# Digital_Inputs.net
KiCad netlist of a schematic drawn in Altium Designer
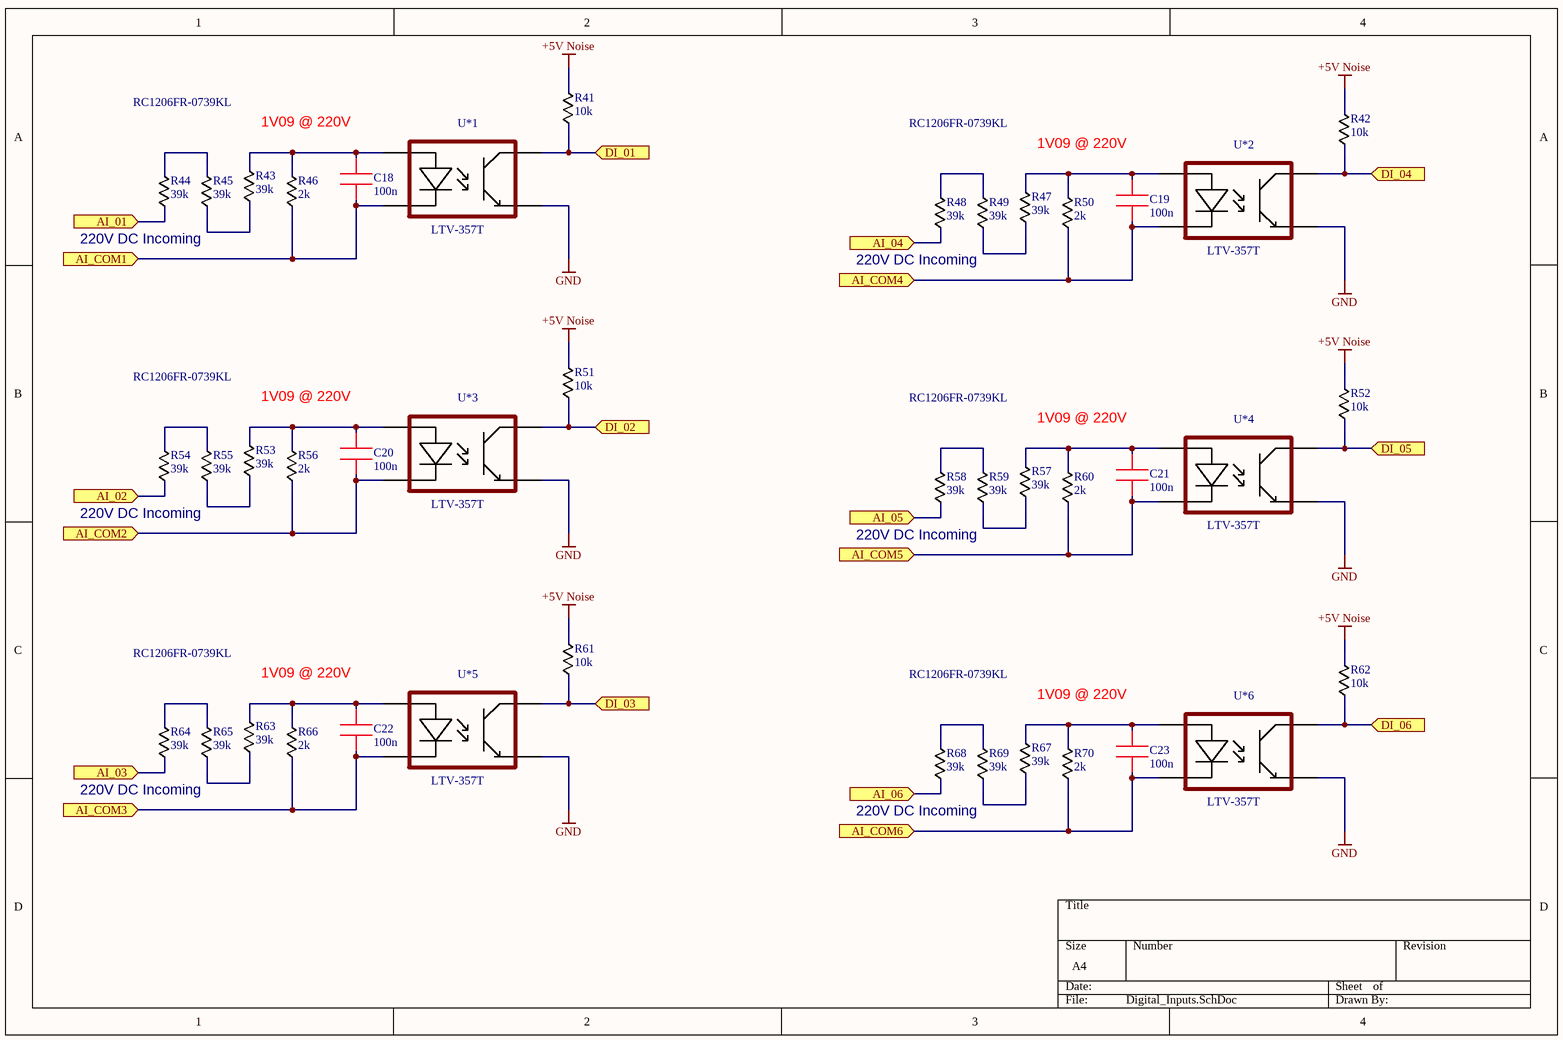
[diagram p0: Digital_Inputs.SchDoc]

(export (version "E")
  (design (tool "Eeschema 10.0.6"))
  (components
    (comp (ref "C18")
      (value "100n")
      (footprint "0603")
      (description "CC0603KRX7R9BB104")
      (libsource (lib "kontr") (part "0603 CAP"))
    )
    (comp (ref "C19")
      (value "100n")
      (footprint "0603")
      (description "CC0603KRX7R9BB104")
      (libsource (lib "kontr") (part "0603 CAP"))
    )
    (comp (ref "C20")
      (value "100n")
      (footprint "0603")
      (description "CC0603KRX7R9BB104")
      (libsource (lib "kontr") (part "0603 CAP"))
    )
    (comp (ref "C21")
      (value "100n")
      (footprint "0603")
      (description "CC0603KRX7R9BB104")
      (libsource (lib "kontr") (part "0603 CAP"))
    )
    (comp (ref "C22")
      (value "100n")
      (footprint "0603")
      (description "CC0603KRX7R9BB104")
      (libsource (lib "kontr") (part "0603 CAP"))
    )
    (comp (ref "C23")
      (value "100n")
      (footprint "0603")
      (description "CC0603KRX7R9BB104")
      (libsource (lib "kontr") (part "0603 CAP"))
    )
    (comp (ref "R41")
      (value "10k")
      (footprint "0603")
      (description "RT0603FRE0710KL")
      (libsource (lib "kontr") (part "0603 RES"))
    )
    (comp (ref "R42")
      (value "10k")
      (footprint "0603")
      (description "RT0603FRE0710KL")
      (libsource (lib "kontr") (part "0603 RES"))
    )
    (comp (ref "R43")
      (value "39k")
      (footprint "1206")
      (description "RC1206FR-0739KL")
      (libsource (lib "kontr") (part "1206 R"))
    )
    (comp (ref "R44")
      (value "39k")
      (footprint "1206")
      (description "RC1206FR-0739KL")
      (libsource (lib "kontr") (part "1206 R"))
    )
    (comp (ref "R45")
      (value "39k")
      (footprint "1206")
      (description "RC1206FR-0739KL")
      (libsource (lib "kontr") (part "1206 R"))
    )
    (comp (ref "R46")
      (value "2k")
      (footprint "1206")
      (description "RC1206FR-072KL")
      (libsource (lib "kontr") (part "1206 R"))
    )
    (comp (ref "R47")
      (value "39k")
      (footprint "1206")
      (description "RC1206FR-0739KL")
      (libsource (lib "kontr") (part "1206 R"))
    )
    (comp (ref "R48")
      (value "39k")
      (footprint "1206")
      (description "RC1206FR-0739KL")
      (libsource (lib "kontr") (part "1206 R"))
    )
    (comp (ref "R49")
      (value "39k")
      (footprint "1206")
      (description "RC1206FR-0739KL")
      (libsource (lib "kontr") (part "1206 R"))
    )
    (comp (ref "R50")
      (value "2k")
      (footprint "1206")
      (description "RC1206FR-072KL")
      (libsource (lib "kontr") (part "1206 R"))
    )
    (comp (ref "R51")
      (value "10k")
      (footprint "0603")
      (description "RT0603FRE0710KL")
      (libsource (lib "kontr") (part "0603 RES"))
    )
    (comp (ref "R52")
      (value "10k")
      (footprint "0603")
      (description "RT0603FRE0710KL")
      (libsource (lib "kontr") (part "0603 RES"))
    )
    (comp (ref "R53")
      (value "39k")
      (footprint "1206")
      (description "RC1206FR-0739KL")
      (libsource (lib "kontr") (part "1206 R"))
    )
    (comp (ref "R54")
      (value "39k")
      (footprint "1206")
      (description "RC1206FR-0739KL")
      (libsource (lib "kontr") (part "1206 R"))
    )
    (comp (ref "R55")
      (value "39k")
      (footprint "1206")
      (description "RC1206FR-0739KL")
      (libsource (lib "kontr") (part "1206 R"))
    )
    (comp (ref "R56")
      (value "2k")
      (footprint "1206")
      (description "RC1206FR-072KL")
      (libsource (lib "kontr") (part "1206 R"))
    )
    (comp (ref "R57")
      (value "39k")
      (footprint "1206")
      (description "RC1206FR-0739KL")
      (libsource (lib "kontr") (part "1206 R"))
    )
    (comp (ref "R58")
      (value "39k")
      (footprint "1206")
      (description "RC1206FR-0739KL")
      (libsource (lib "kontr") (part "1206 R"))
    )
    (comp (ref "R59")
      (value "39k")
      (footprint "1206")
      (description "RC1206FR-0739KL")
      (libsource (lib "kontr") (part "1206 R"))
    )
    (comp (ref "R60")
      (value "2k")
      (footprint "1206")
      (description "RC1206FR-072KL")
      (libsource (lib "kontr") (part "1206 R"))
    )
    (comp (ref "R61")
      (value "10k")
      (footprint "0603")
      (description "RT0603FRE0710KL")
      (libsource (lib "kontr") (part "0603 RES"))
    )
    (comp (ref "R62")
      (value "10k")
      (footprint "0603")
      (description "RT0603FRE0710KL")
      (libsource (lib "kontr") (part "0603 RES"))
    )
    (comp (ref "R63")
      (value "39k")
      (footprint "1206")
      (description "RC1206FR-0739KL")
      (libsource (lib "kontr") (part "1206 R"))
    )
    (comp (ref "R64")
      (value "39k")
      (footprint "1206")
      (description "RC1206FR-0739KL")
      (libsource (lib "kontr") (part "1206 R"))
    )
    (comp (ref "R65")
      (value "39k")
      (footprint "1206")
      (description "RC1206FR-0739KL")
      (libsource (lib "kontr") (part "1206 R"))
    )
    (comp (ref "R66")
      (value "2k")
      (footprint "1206")
      (description "RC1206FR-072KL")
      (libsource (lib "kontr") (part "1206 R"))
    )
    (comp (ref "R67")
      (value "39k")
      (footprint "1206")
      (description "RC1206FR-0739KL")
      (libsource (lib "kontr") (part "1206 R"))
    )
    (comp (ref "R68")
      (value "39k")
      (footprint "1206")
      (description "RC1206FR-0739KL")
      (libsource (lib "kontr") (part "1206 R"))
    )
    (comp (ref "R69")
      (value "39k")
      (footprint "1206")
      (description "RC1206FR-0739KL")
      (libsource (lib "kontr") (part "1206 R"))
    )
    (comp (ref "R70")
      (value "2k")
      (footprint "1206")
      (description "RC1206FR-072KL")
      (libsource (lib "kontr") (part "1206 R"))
    )
    (comp (ref "U*1")
      (value "LTV-357T")
      (footprint "levin:SOP-4")
      (libsource (lib "levin") (part "LTV-357T"))
    )
    (comp (ref "U*2")
      (value "LTV-357T")
      (footprint "levin:SOP-4")
      (libsource (lib "levin") (part "LTV-357T"))
    )
    (comp (ref "U*3")
      (value "LTV-357T")
      (footprint "levin:SOP-4")
      (libsource (lib "levin") (part "LTV-357T"))
    )
    (comp (ref "U*4")
      (value "LTV-357T")
      (footprint "levin:SOP-4")
      (libsource (lib "levin") (part "LTV-357T"))
    )
    (comp (ref "U*5")
      (value "LTV-357T")
      (footprint "levin:SOP-4")
      (libsource (lib "levin") (part "LTV-357T"))
    )
    (comp (ref "U*6")
      (value "LTV-357T")
      (footprint "levin:SOP-4")
      (libsource (lib "levin") (part "LTV-357T"))
    )
  )
  (nets
    (net (code "1") (name "+5V Noise") (class "Default")
      (node (ref "R41") (pin "2") (pintype "passive"))
      (node (ref "R42") (pin "2") (pintype "passive"))
      (node (ref "R51") (pin "2") (pintype "passive"))
      (node (ref "R52") (pin "2") (pintype "passive"))
      (node (ref "R61") (pin "2") (pintype "passive"))
      (node (ref "R62") (pin "2") (pintype "passive"))
    )
    (net (code "2") (name "/AI_01") (class "Default") (node (ref "R44") (pin "1") (pintype "passive")))
    (net (code "3") (name "/AI_02") (class "Default") (node (ref "R54") (pin "1") (pintype "passive")))
    (net (code "4") (name "/AI_03") (class "Default") (node (ref "R64") (pin "1") (pintype "passive")))
    (net (code "5") (name "/AI_04") (class "Default") (node (ref "R48") (pin "1") (pintype "passive")))
    (net (code "6") (name "/AI_05") (class "Default") (node (ref "R58") (pin "1") (pintype "passive")))
    (net (code "7") (name "/AI_06") (class "Default") (node (ref "R68") (pin "1") (pintype "passive")))
    (net (code "8") (name "/AI_COM1") (class "Default")
      (node (ref "C18") (pin "1") (pinfunction "1_1") (pintype "passive"))
      (node (ref "R46") (pin "1") (pintype "passive"))
      (node (ref "U*1") (pin "Cathode") (pinfunction "C_Cathode") (pintype "passive"))
    )
    (net (code "9") (name "/AI_COM2") (class "Default")
      (node (ref "C20") (pin "1") (pinfunction "1_1") (pintype "passive"))
      (node (ref "R56") (pin "1") (pintype "passive"))
      (node (ref "U*3") (pin "Cathode") (pinfunction "C_Cathode") (pintype "passive"))
    )
    (net (code "10") (name "/AI_COM3") (class "Default")
      (node (ref "C22") (pin "1") (pinfunction "1_1") (pintype "passive"))
      (node (ref "R66") (pin "1") (pintype "passive"))
      (node (ref "U*5") (pin "Cathode") (pinfunction "C_Cathode") (pintype "passive"))
    )
    (net (code "11") (name "/AI_COM4") (class "Default")
      (node (ref "C19") (pin "1") (pinfunction "1_1") (pintype "passive"))
      (node (ref "R50") (pin "1") (pintype "passive"))
      (node (ref "U*2") (pin "Cathode") (pinfunction "C_Cathode") (pintype "passive"))
    )
    (net (code "12") (name "/AI_COM5") (class "Default")
      (node (ref "C21") (pin "1") (pinfunction "1_1") (pintype "passive"))
      (node (ref "R60") (pin "1") (pintype "passive"))
      (node (ref "U*4") (pin "Cathode") (pinfunction "C_Cathode") (pintype "passive"))
    )
    (net (code "13") (name "/AI_COM6") (class "Default")
      (node (ref "C23") (pin "1") (pinfunction "1_1") (pintype "passive"))
      (node (ref "R70") (pin "1") (pintype "passive"))
      (node (ref "U*6") (pin "Cathode") (pinfunction "C_Cathode") (pintype "passive"))
    )
    (net (code "14") (name "/DI_01") (class "Default")
      (node (ref "R41") (pin "1") (pintype "passive"))
      (node (ref "U*1") (pin "Collector") (pinfunction "C_Collector") (pintype "passive"))
    )
    (net (code "15") (name "/DI_02") (class "Default")
      (node (ref "R51") (pin "1") (pintype "passive"))
      (node (ref "U*3") (pin "Collector") (pinfunction "C_Collector") (pintype "passive"))
    )
    (net (code "16") (name "/DI_03") (class "Default")
      (node (ref "R61") (pin "1") (pintype "passive"))
      (node (ref "U*5") (pin "Collector") (pinfunction "C_Collector") (pintype "passive"))
    )
    (net (code "17") (name "/DI_04") (class "Default")
      (node (ref "R42") (pin "1") (pintype "passive"))
      (node (ref "U*2") (pin "Collector") (pinfunction "C_Collector") (pintype "passive"))
    )
    (net (code "18") (name "/DI_05") (class "Default")
      (node (ref "R52") (pin "1") (pintype "passive"))
      (node (ref "U*4") (pin "Collector") (pinfunction "C_Collector") (pintype "passive"))
    )
    (net (code "19") (name "/DI_06") (class "Default")
      (node (ref "R62") (pin "1") (pintype "passive"))
      (node (ref "U*6") (pin "Collector") (pinfunction "C_Collector") (pintype "passive"))
    )
    (net (code "20") (name "GND") (class "Default")
      (node (ref "U*1") (pin "Emmiter") (pinfunction "E_Emmiter") (pintype "passive"))
      (node (ref "U*2") (pin "Emmiter") (pinfunction "E_Emmiter") (pintype "passive"))
      (node (ref "U*3") (pin "Emmiter") (pinfunction "E_Emmiter") (pintype "passive"))
      (node (ref "U*4") (pin "Emmiter") (pinfunction "E_Emmiter") (pintype "passive"))
      (node (ref "U*5") (pin "Emmiter") (pinfunction "E_Emmiter") (pintype "passive"))
      (node (ref "U*6") (pin "Emmiter") (pinfunction "E_Emmiter") (pintype "passive"))
    )
    (net (code "21") (name "Net-(R43-Pad1)") (class "Default")
      (node (ref "R43") (pin "1") (pintype "passive"))
      (node (ref "R45") (pin "1") (pintype "passive"))
    )
    (net (code "22") (name "Net-(R44-Pad2)") (class "Default")
      (node (ref "R44") (pin "2") (pintype "passive"))
      (node (ref "R45") (pin "2") (pintype "passive"))
    )
    (net (code "23") (name "Net-(R47-Pad1)") (class "Default")
      (node (ref "R47") (pin "1") (pintype "passive"))
      (node (ref "R49") (pin "1") (pintype "passive"))
    )
    (net (code "24") (name "Net-(R48-Pad2)") (class "Default")
      (node (ref "R48") (pin "2") (pintype "passive"))
      (node (ref "R49") (pin "2") (pintype "passive"))
    )
    (net (code "25") (name "Net-(R53-Pad1)") (class "Default")
      (node (ref "R53") (pin "1") (pintype "passive"))
      (node (ref "R55") (pin "1") (pintype "passive"))
    )
    (net (code "26") (name "Net-(R54-Pad2)") (class "Default")
      (node (ref "R54") (pin "2") (pintype "passive"))
      (node (ref "R55") (pin "2") (pintype "passive"))
    )
    (net (code "27") (name "Net-(R57-Pad1)") (class "Default")
      (node (ref "R57") (pin "1") (pintype "passive"))
      (node (ref "R59") (pin "1") (pintype "passive"))
    )
    (net (code "28") (name "Net-(R58-Pad2)") (class "Default")
      (node (ref "R58") (pin "2") (pintype "passive"))
      (node (ref "R59") (pin "2") (pintype "passive"))
    )
    (net (code "29") (name "Net-(R63-Pad1)") (class "Default")
      (node (ref "R63") (pin "1") (pintype "passive"))
      (node (ref "R65") (pin "1") (pintype "passive"))
    )
    (net (code "30") (name "Net-(R64-Pad2)") (class "Default")
      (node (ref "R64") (pin "2") (pintype "passive"))
      (node (ref "R65") (pin "2") (pintype "passive"))
    )
    (net (code "31") (name "Net-(R67-Pad1)") (class "Default")
      (node (ref "R67") (pin "1") (pintype "passive"))
      (node (ref "R69") (pin "1") (pintype "passive"))
    )
    (net (code "32") (name "Net-(R68-Pad2)") (class "Default")
      (node (ref "R68") (pin "2") (pintype "passive"))
      (node (ref "R69") (pin "2") (pintype "passive"))
    )
    (net (code "33") (name "Net-(U*1-A)") (class "Default")
      (node (ref "C18") (pin "2") (pinfunction "2_2") (pintype "passive"))
      (node (ref "R43") (pin "2") (pintype "passive"))
      (node (ref "R46") (pin "2") (pintype "passive"))
      (node (ref "U*1") (pin "Anode") (pinfunction "A_Anode") (pintype "passive"))
    )
    (net (code "34") (name "Net-(U*2-A)") (class "Default")
      (node (ref "C19") (pin "2") (pinfunction "2_2") (pintype "passive"))
      (node (ref "R47") (pin "2") (pintype "passive"))
      (node (ref "R50") (pin "2") (pintype "passive"))
      (node (ref "U*2") (pin "Anode") (pinfunction "A_Anode") (pintype "passive"))
    )
    (net (code "35") (name "Net-(U*3-A)") (class "Default")
      (node (ref "C20") (pin "2") (pinfunction "2_2") (pintype "passive"))
      (node (ref "R53") (pin "2") (pintype "passive"))
      (node (ref "R56") (pin "2") (pintype "passive"))
      (node (ref "U*3") (pin "Anode") (pinfunction "A_Anode") (pintype "passive"))
    )
    (net (code "36") (name "Net-(U*4-A)") (class "Default")
      (node (ref "C21") (pin "2") (pinfunction "2_2") (pintype "passive"))
      (node (ref "R57") (pin "2") (pintype "passive"))
      (node (ref "R60") (pin "2") (pintype "passive"))
      (node (ref "U*4") (pin "Anode") (pinfunction "A_Anode") (pintype "passive"))
    )
    (net (code "37") (name "Net-(U*5-A)") (class "Default")
      (node (ref "C22") (pin "2") (pinfunction "2_2") (pintype "passive"))
      (node (ref "R63") (pin "2") (pintype "passive"))
      (node (ref "R66") (pin "2") (pintype "passive"))
      (node (ref "U*5") (pin "Anode") (pinfunction "A_Anode") (pintype "passive"))
    )
    (net (code "38") (name "Net-(U*6-A)") (class "Default")
      (node (ref "C23") (pin "2") (pinfunction "2_2") (pintype "passive"))
      (node (ref "R67") (pin "2") (pintype "passive"))
      (node (ref "R70") (pin "2") (pintype "passive"))
      (node (ref "U*6") (pin "Anode") (pinfunction "A_Anode") (pintype "passive"))
    )
  )
)
